# B201.net
KiCad netlist of a schematic drawn in EAGLE
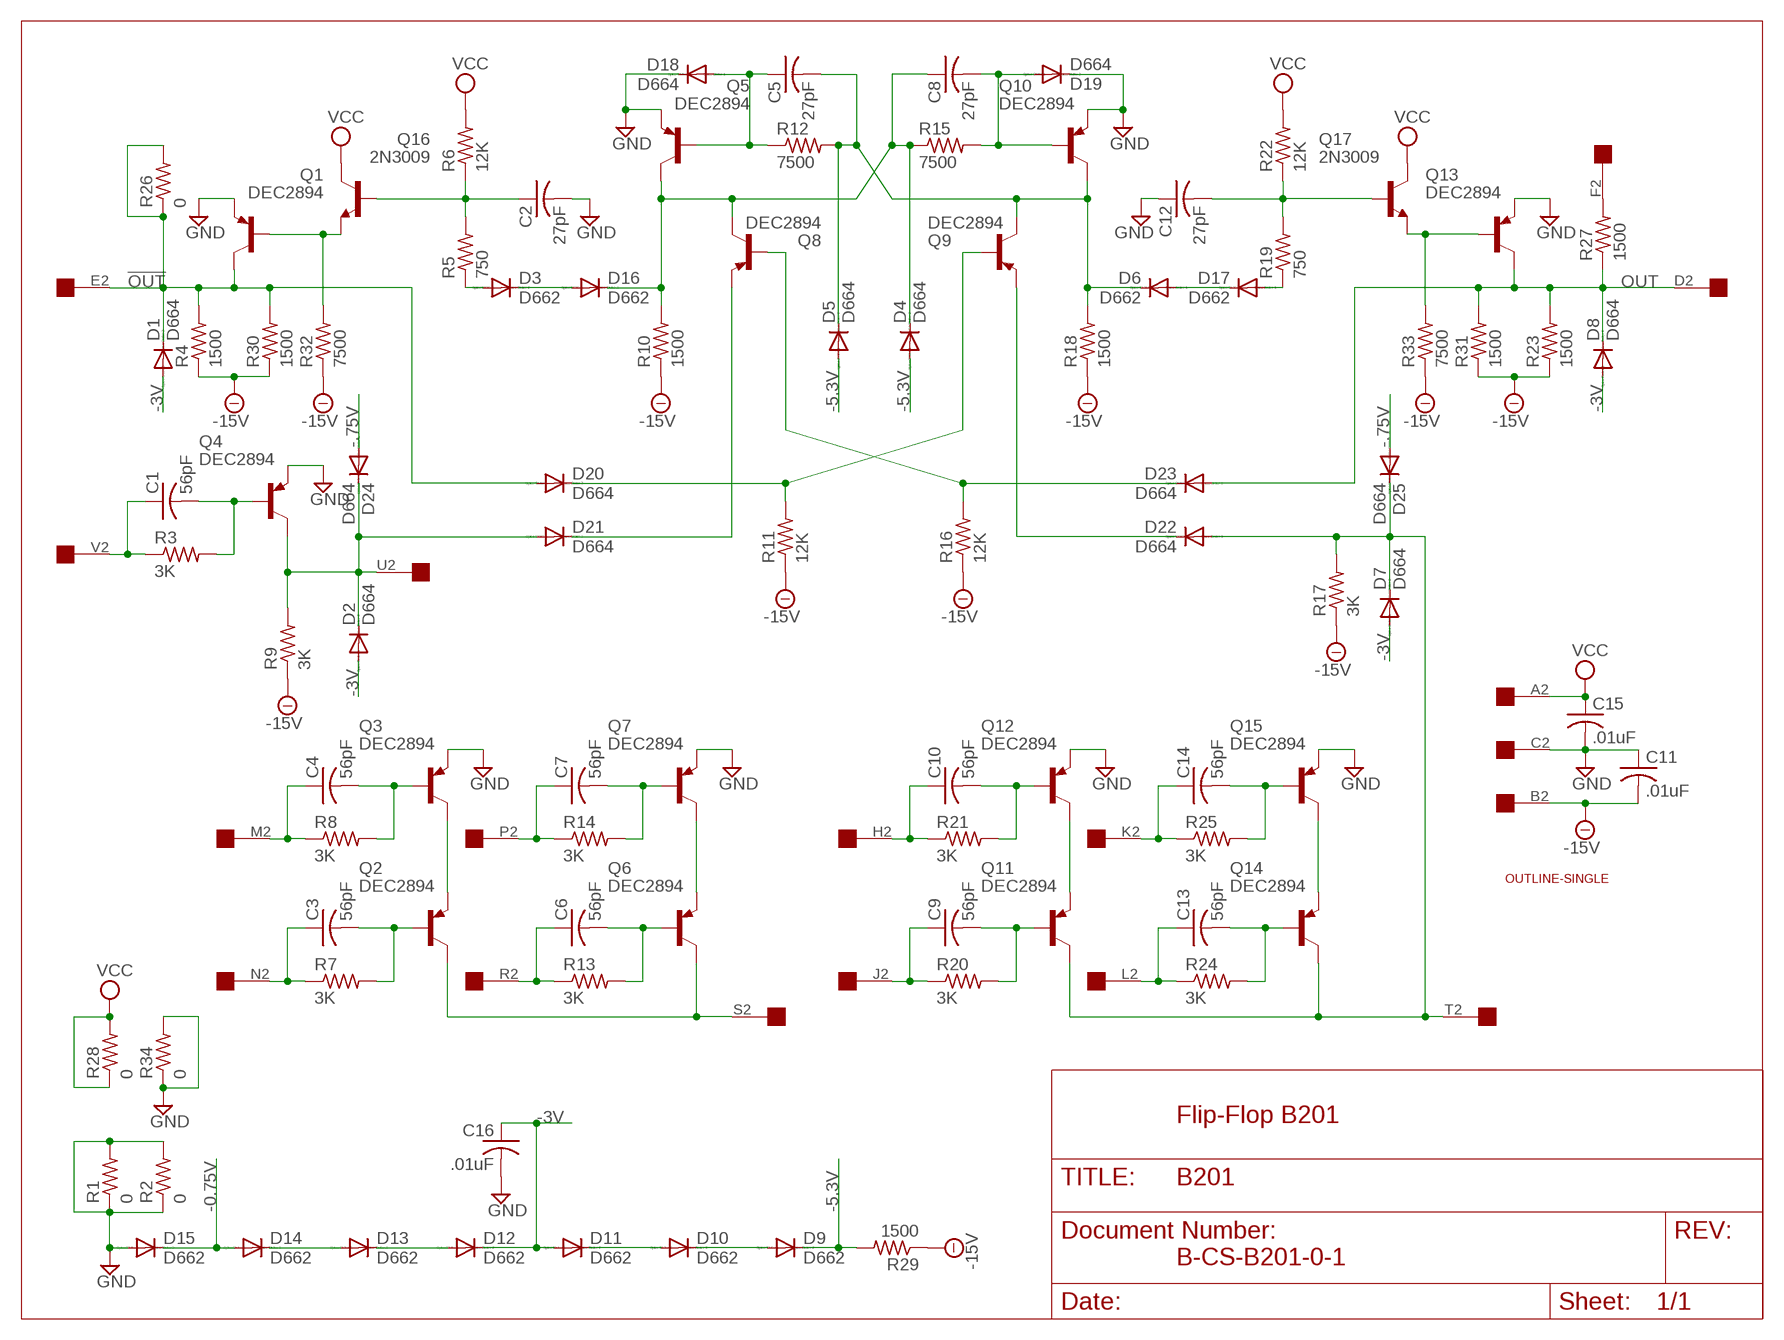
[diagram p0: schematic, sheet 1]

(export (version "E")
  (design (tool "Eeschema 10.0.6"))
  (components
    (comp (ref "C1")
      (value "56pF")
      (footprint "eagle-import:C063-025X075")
      (libsource (lib "eagle-import") (part "C-US"))
    )
    (comp (ref "C2")
      (value "27pF")
      (footprint "eagle-import:C063-025X075")
      (libsource (lib "eagle-import") (part "C-US"))
    )
    (comp (ref "C3")
      (value "56pF")
      (footprint "eagle-import:C063-025X075")
      (libsource (lib "eagle-import") (part "C-US"))
    )
    (comp (ref "C4")
      (value "56pF")
      (footprint "eagle-import:C063-025X075")
      (libsource (lib "eagle-import") (part "C-US"))
    )
    (comp (ref "C5")
      (value "27pF")
      (footprint "eagle-import:C063-025X075")
      (libsource (lib "eagle-import") (part "C-US"))
    )
    (comp (ref "C6")
      (value "56pF")
      (footprint "eagle-import:C063-025X075")
      (libsource (lib "eagle-import") (part "C-US"))
    )
    (comp (ref "C7")
      (value "56pF")
      (footprint "eagle-import:C063-025X075")
      (libsource (lib "eagle-import") (part "C-US"))
    )
    (comp (ref "C8")
      (value "27pF")
      (footprint "eagle-import:C063-025X075")
      (libsource (lib "eagle-import") (part "C-US"))
    )
    (comp (ref "C9")
      (value "56pF")
      (footprint "eagle-import:C063-025X075")
      (libsource (lib "eagle-import") (part "C-US"))
    )
    (comp (ref "C10")
      (value "56pF")
      (footprint "eagle-import:C063-025X075")
      (libsource (lib "eagle-import") (part "C-US"))
    )
    (comp (ref "C11")
      (value ".01uF")
      (footprint "eagle-import:C063-025X075")
      (libsource (lib "eagle-import") (part "C-US"))
    )
    (comp (ref "C12")
      (value "27pF")
      (footprint "eagle-import:C063-025X075")
      (libsource (lib "eagle-import") (part "C-US"))
    )
    (comp (ref "C13")
      (value "56pF")
      (footprint "eagle-import:C063-025X075")
      (libsource (lib "eagle-import") (part "C-US"))
    )
    (comp (ref "C14")
      (value "56pF")
      (footprint "eagle-import:C063-025X075")
      (libsource (lib "eagle-import") (part "C-US"))
    )
    (comp (ref "C15")
      (value ".01uF")
      (footprint "eagle-import:C063-025X075")
      (libsource (lib "eagle-import") (part "C-US"))
    )
    (comp (ref "C16")
      (value ".01uF")
      (footprint "eagle-import:C063-025X075")
      (libsource (lib "eagle-import") (part "C-US"))
    )
    (comp (ref "D1")
      (value "D664")
      (footprint "eagle-import:DO35-10")
      (libsource (lib "eagle-import") (part "DIODE-DO35-10"))
    )
    (comp (ref "D2")
      (value "D664")
      (footprint "eagle-import:DO35-10")
      (libsource (lib "eagle-import") (part "DIODE-DO35-10"))
    )
    (comp (ref "D3")
      (value "D662")
      (footprint "eagle-import:DO35-10")
      (libsource (lib "eagle-import") (part "DIODE-DO35-10"))
    )
    (comp (ref "D4")
      (value "D664")
      (footprint "eagle-import:DO35-10")
      (libsource (lib "eagle-import") (part "DIODE-DO35-10"))
    )
    (comp (ref "D5")
      (value "D664")
      (footprint "eagle-import:DO35-10")
      (libsource (lib "eagle-import") (part "DIODE-DO35-10"))
    )
    (comp (ref "D6")
      (value "D662")
      (footprint "eagle-import:DO35-10")
      (libsource (lib "eagle-import") (part "DIODE-DO35-10"))
    )
    (comp (ref "D7")
      (value "D664")
      (footprint "eagle-import:DO35-10")
      (libsource (lib "eagle-import") (part "DIODE-DO35-10"))
    )
    (comp (ref "D8")
      (value "D664")
      (footprint "eagle-import:DO35-10")
      (libsource (lib "eagle-import") (part "DIODE-DO35-10"))
    )
    (comp (ref "D9")
      (value "D662")
      (footprint "eagle-import:DO35-10")
      (libsource (lib "eagle-import") (part "DIODE-DO35-10"))
    )
    (comp (ref "D10")
      (value "D662")
      (footprint "eagle-import:DO35-10")
      (libsource (lib "eagle-import") (part "DIODE-DO35-10"))
    )
    (comp (ref "D11")
      (value "D662")
      (footprint "eagle-import:DO35-10")
      (libsource (lib "eagle-import") (part "DIODE-DO35-10"))
    )
    (comp (ref "D12")
      (value "D662")
      (footprint "eagle-import:DO35-10")
      (libsource (lib "eagle-import") (part "DIODE-DO35-10"))
    )
    (comp (ref "D13")
      (value "D662")
      (footprint "eagle-import:DO35-10")
      (libsource (lib "eagle-import") (part "DIODE-DO35-10"))
    )
    (comp (ref "D14")
      (value "D662")
      (footprint "eagle-import:DO35-10")
      (libsource (lib "eagle-import") (part "DIODE-DO35-10"))
    )
    (comp (ref "D15")
      (value "D662")
      (footprint "eagle-import:DO35-10")
      (libsource (lib "eagle-import") (part "DIODE-DO35-10"))
    )
    (comp (ref "D16")
      (value "D662")
      (footprint "eagle-import:DO35-10")
      (libsource (lib "eagle-import") (part "DIODE-DO35-10"))
    )
    (comp (ref "D17")
      (value "D662")
      (footprint "eagle-import:DO35-10")
      (libsource (lib "eagle-import") (part "DIODE-DO35-10"))
    )
    (comp (ref "D18")
      (value "D664")
      (footprint "eagle-import:DO35-10")
      (libsource (lib "eagle-import") (part "DIODE-DO35-10"))
    )
    (comp (ref "D19")
      (value "D664")
      (footprint "eagle-import:DO35-10")
      (libsource (lib "eagle-import") (part "DIODE-DO35-10"))
    )
    (comp (ref "D20")
      (value "D664")
      (footprint "eagle-import:DO35-10")
      (libsource (lib "eagle-import") (part "DIODE-DO35-10"))
    )
    (comp (ref "D21")
      (value "D664")
      (footprint "eagle-import:DO35-10")
      (libsource (lib "eagle-import") (part "DIODE-DO35-10"))
    )
    (comp (ref "D22")
      (value "D664")
      (footprint "eagle-import:DO35-10")
      (libsource (lib "eagle-import") (part "DIODE-DO35-10"))
    )
    (comp (ref "D23")
      (value "D664")
      (footprint "eagle-import:DO35-10")
      (libsource (lib "eagle-import") (part "DIODE-DO35-10"))
    )
    (comp (ref "D24")
      (value "D664")
      (footprint "eagle-import:DO35-10")
      (libsource (lib "eagle-import") (part "DIODE-DO35-10"))
    )
    (comp (ref "D25")
      (value "D664")
      (footprint "eagle-import:DO35-10")
      (libsource (lib "eagle-import") (part "DIODE-DO35-10"))
    )
    (comp (ref "Q1")
      (value "DEC2894")
      (footprint "eagle-import:TO5")
      (libsource (lib "eagle-import") (part "-PNP-TO5"))
    )
    (comp (ref "Q2")
      (value "DEC2894")
      (footprint "eagle-import:TO5")
      (libsource (lib "eagle-import") (part "-PNP-TO5"))
    )
    (comp (ref "Q3")
      (value "DEC2894")
      (footprint "eagle-import:TO5")
      (libsource (lib "eagle-import") (part "-PNP-TO5"))
    )
    (comp (ref "Q4")
      (value "DEC2894")
      (footprint "eagle-import:TO5")
      (libsource (lib "eagle-import") (part "-PNP-TO5"))
    )
    (comp (ref "Q5")
      (value "DEC2894")
      (footprint "eagle-import:TO5")
      (libsource (lib "eagle-import") (part "-PNP-TO5"))
    )
    (comp (ref "Q6")
      (value "DEC2894")
      (footprint "eagle-import:TO5")
      (libsource (lib "eagle-import") (part "-PNP-TO5"))
    )
    (comp (ref "Q7")
      (value "DEC2894")
      (footprint "eagle-import:TO5")
      (libsource (lib "eagle-import") (part "-PNP-TO5"))
    )
    (comp (ref "Q8")
      (value "DEC2894")
      (footprint "eagle-import:TO5")
      (libsource (lib "eagle-import") (part "-PNP-TO5"))
    )
    (comp (ref "Q9")
      (value "DEC2894")
      (footprint "eagle-import:TO5")
      (libsource (lib "eagle-import") (part "-PNP-TO5"))
    )
    (comp (ref "Q10")
      (value "DEC2894")
      (footprint "eagle-import:TO5")
      (libsource (lib "eagle-import") (part "-PNP-TO5"))
    )
    (comp (ref "Q11")
      (value "DEC2894")
      (footprint "eagle-import:TO5")
      (libsource (lib "eagle-import") (part "-PNP-TO5"))
    )
    (comp (ref "Q12")
      (value "DEC2894")
      (footprint "eagle-import:TO5")
      (libsource (lib "eagle-import") (part "-PNP-TO5"))
    )
    (comp (ref "Q13")
      (value "DEC2894")
      (footprint "eagle-import:TO5")
      (libsource (lib "eagle-import") (part "-PNP-TO5"))
    )
    (comp (ref "Q14")
      (value "DEC2894")
      (footprint "eagle-import:TO5")
      (libsource (lib "eagle-import") (part "-PNP-TO5"))
    )
    (comp (ref "Q15")
      (value "DEC2894")
      (footprint "eagle-import:TO5")
      (libsource (lib "eagle-import") (part "-PNP-TO5"))
    )
    (comp (ref "Q16")
      (value "2N3009")
      (footprint "eagle-import:TO5")
      (libsource (lib "eagle-import") (part "-NPN-TO5"))
    )
    (comp (ref "Q17")
      (value "2N3009")
      (footprint "eagle-import:TO5")
      (libsource (lib "eagle-import") (part "-NPN-TO5"))
    )
    (comp (ref "R1")
      (value "0")
      (footprint "eagle-import:0207_10")
      (libsource (lib "eagle-import") (part "R-US_0207/10"))
    )
    (comp (ref "R2")
      (value "0")
      (footprint "eagle-import:0207_10")
      (libsource (lib "eagle-import") (part "R-US_0207/10"))
    )
    (comp (ref "R3")
      (value "3K")
      (footprint "eagle-import:0207_10")
      (libsource (lib "eagle-import") (part "R-US_0207/10"))
    )
    (comp (ref "R4")
      (value "1500")
      (footprint "eagle-import:0207_10")
      (libsource (lib "eagle-import") (part "R-US_0207/10"))
    )
    (comp (ref "R5")
      (value "750")
      (footprint "eagle-import:0207_10")
      (libsource (lib "eagle-import") (part "R-US_0207/10"))
    )
    (comp (ref "R6")
      (value "12K")
      (footprint "eagle-import:0207_10")
      (libsource (lib "eagle-import") (part "R-US_0207/10"))
    )
    (comp (ref "R7")
      (value "3K")
      (footprint "eagle-import:0207_10")
      (libsource (lib "eagle-import") (part "R-US_0207/10"))
    )
    (comp (ref "R8")
      (value "3K")
      (footprint "eagle-import:0207_10")
      (libsource (lib "eagle-import") (part "R-US_0207/10"))
    )
    (comp (ref "R9")
      (value "3K")
      (footprint "eagle-import:0207_10")
      (libsource (lib "eagle-import") (part "R-US_0207/10"))
    )
    (comp (ref "R10")
      (value "1500")
      (footprint "eagle-import:0207_10")
      (libsource (lib "eagle-import") (part "R-US_0207/10"))
    )
    (comp (ref "R11")
      (value "12K")
      (footprint "eagle-import:0207_10")
      (libsource (lib "eagle-import") (part "R-US_0207/10"))
    )
    (comp (ref "R12")
      (value "7500")
      (footprint "eagle-import:0207_10")
      (libsource (lib "eagle-import") (part "R-US_0207/10"))
    )
    (comp (ref "R13")
      (value "3K")
      (footprint "eagle-import:0207_10")
      (libsource (lib "eagle-import") (part "R-US_0207/10"))
    )
    (comp (ref "R14")
      (value "3K")
      (footprint "eagle-import:0207_10")
      (libsource (lib "eagle-import") (part "R-US_0207/10"))
    )
    (comp (ref "R15")
      (value "7500")
      (footprint "eagle-import:0207_10")
      (libsource (lib "eagle-import") (part "R-US_0207/10"))
    )
    (comp (ref "R16")
      (value "12K")
      (footprint "eagle-import:0207_10")
      (libsource (lib "eagle-import") (part "R-US_0207/10"))
    )
    (comp (ref "R17")
      (value "3K")
      (footprint "eagle-import:0207_10")
      (libsource (lib "eagle-import") (part "R-US_0207/10"))
    )
    (comp (ref "R18")
      (value "1500")
      (footprint "eagle-import:0207_10")
      (libsource (lib "eagle-import") (part "R-US_0207/10"))
    )
    (comp (ref "R19")
      (value "750")
      (footprint "eagle-import:0207_10")
      (libsource (lib "eagle-import") (part "R-US_0207/10"))
    )
    (comp (ref "R20")
      (value "3K")
      (footprint "eagle-import:0207_10")
      (libsource (lib "eagle-import") (part "R-US_0207/10"))
    )
    (comp (ref "R21")
      (value "3K")
      (footprint "eagle-import:0207_10")
      (libsource (lib "eagle-import") (part "R-US_0207/10"))
    )
    (comp (ref "R22")
      (value "12K")
      (footprint "eagle-import:0207_10")
      (libsource (lib "eagle-import") (part "R-US_0207/10"))
    )
    (comp (ref "R23")
      (value "1500")
      (footprint "eagle-import:0207_10")
      (libsource (lib "eagle-import") (part "R-US_0207/10"))
    )
    (comp (ref "R24")
      (value "3K")
      (footprint "eagle-import:0207_10")
      (libsource (lib "eagle-import") (part "R-US_0207/10"))
    )
    (comp (ref "R25")
      (value "3K")
      (footprint "eagle-import:0207_10")
      (libsource (lib "eagle-import") (part "R-US_0207/10"))
    )
    (comp (ref "R26")
      (value "0")
      (footprint "eagle-import:0207_10")
      (libsource (lib "eagle-import") (part "R-US_0207/10"))
    )
    (comp (ref "R27")
      (value "1500")
      (footprint "eagle-import:0207_10")
      (libsource (lib "eagle-import") (part "R-US_0207/10"))
    )
    (comp (ref "R28")
      (value "0")
      (footprint "eagle-import:0207_10")
      (libsource (lib "eagle-import") (part "R-US_0207/10"))
    )
    (comp (ref "R29")
      (value "1500")
      (footprint "eagle-import:0207_10")
      (libsource (lib "eagle-import") (part "R-US_0207/10"))
    )
    (comp (ref "R30")
      (value "1500")
      (footprint "eagle-import:0207_10")
      (libsource (lib "eagle-import") (part "R-US_0207/10"))
    )
    (comp (ref "R31")
      (value "1500")
      (footprint "eagle-import:0207_10")
      (libsource (lib "eagle-import") (part "R-US_0207/10"))
    )
    (comp (ref "R32")
      (value "7500")
      (footprint "eagle-import:0207_10")
      (libsource (lib "eagle-import") (part "R-US_0207/10"))
    )
    (comp (ref "R33")
      (value "7500")
      (footprint "eagle-import:0207_10")
      (libsource (lib "eagle-import") (part "R-US_0207/10"))
    )
    (comp (ref "R34")
      (value "0")
      (footprint "eagle-import:0207_10")
      (libsource (lib "eagle-import") (part "R-US_0207/10"))
    )
    (comp (ref "U$1")
      (value "OUTLINE-SINGLE")
      (footprint "eagle-import:SINGLE")
      (libsource (lib "eagle-import") (part "OUTLINE-SINGLE"))
    )
    (comp (ref "U$2")
      (value "EDGE-1")
      (footprint "eagle-import:EDGE-CON1")
      (libsource (lib "eagle-import") (part "EDGE-1"))
    )
  )
  (nets
    (net (code "1") (name "-15V") (class "Default")
      (node (ref "C11") (pin "2") (pinfunction "2_2") (pintype "passive"))
      (node (ref "R10") (pin "1") (pinfunction "1_1") (pintype "passive"))
      (node (ref "R11") (pin "1") (pinfunction "1_1") (pintype "passive"))
      (node (ref "R16") (pin "1") (pinfunction "1_1") (pintype "passive"))
      (node (ref "R17") (pin "1") (pinfunction "1_1") (pintype "passive"))
      (node (ref "R18") (pin "1") (pinfunction "1_1") (pintype "passive"))
      (node (ref "R23") (pin "1") (pinfunction "1_1") (pintype "passive"))
      (node (ref "R29") (pin "1") (pinfunction "1_1") (pintype "passive"))
      (node (ref "R30") (pin "1") (pinfunction "1_1") (pintype "passive"))
      (node (ref "R31") (pin "1") (pinfunction "1_1") (pintype "passive"))
      (node (ref "R32") (pin "1") (pinfunction "1_1") (pintype "passive"))
      (node (ref "R33") (pin "1") (pinfunction "1_1") (pintype "passive"))
      (node (ref "R4") (pin "1") (pinfunction "1_1") (pintype "passive"))
      (node (ref "R9") (pin "1") (pinfunction "1_1") (pintype "passive"))
      (node (ref "U$2") (pin "B2") (pinfunction "1_B2") (pintype "bidirectional"))
    )
    (net (code "2") (name "/-.75V") (class "Default")
      (node (ref "D24") (pin "A") (pinfunction "A_A") (pintype "passive"))
      (node (ref "D25") (pin "A") (pinfunction "A_A") (pintype "passive"))
    )
    (net (code "3") (name "/-0.75V") (class "Default")
      (node (ref "D14") (pin "A") (pinfunction "A_A") (pintype "passive"))
      (node (ref "D15") (pin "C") (pinfunction "C_C") (pintype "passive"))
    )
    (net (code "4") (name "/-3V") (class "Default")
      (node (ref "C16") (pin "1") (pinfunction "1_1") (pintype "passive"))
      (node (ref "D1") (pin "A") (pinfunction "A_A") (pintype "passive"))
      (node (ref "D11") (pin "A") (pinfunction "A_A") (pintype "passive"))
      (node (ref "D12") (pin "C") (pinfunction "C_C") (pintype "passive"))
      (node (ref "D2") (pin "A") (pinfunction "A_A") (pintype "passive"))
      (node (ref "D7") (pin "A") (pinfunction "A_A") (pintype "passive"))
      (node (ref "D8") (pin "A") (pinfunction "A_A") (pintype "passive"))
    )
    (net (code "5") (name "/-5.3V") (class "Default")
      (node (ref "D4") (pin "A") (pinfunction "A_A") (pintype "passive"))
      (node (ref "D5") (pin "A") (pinfunction "A_A") (pintype "passive"))
      (node (ref "D9") (pin "C") (pinfunction "C_C") (pintype "passive"))
      (node (ref "R29") (pin "2") (pinfunction "2_2") (pintype "passive"))
    )
    (net (code "6") (name "/OUT") (class "Default")
      (node (ref "D23") (pin "A") (pinfunction "A_A") (pintype "passive"))
      (node (ref "D8") (pin "C") (pinfunction "C_C") (pintype "passive"))
      (node (ref "Q13") (pin "3") (pinfunction "C_3") (pintype "passive"))
      (node (ref "R23") (pin "2") (pinfunction "2_2") (pintype "passive"))
      (node (ref "R27") (pin "1") (pinfunction "1_1") (pintype "passive"))
      (node (ref "R31") (pin "2") (pinfunction "2_2") (pintype "passive"))
      (node (ref "U$2") (pin "D2") (pinfunction "1_D2") (pintype "bidirectional"))
    )
    (net (code "7") (name "/~{OUT}") (class "Default")
      (node (ref "D1") (pin "C") (pinfunction "C_C") (pintype "passive"))
      (node (ref "D20") (pin "A") (pinfunction "A_A") (pintype "passive"))
      (node (ref "Q1") (pin "3") (pinfunction "C_3") (pintype "passive"))
      (node (ref "R26") (pin "1") (pinfunction "1_1") (pintype "passive"))
      (node (ref "R26") (pin "2") (pinfunction "2_2") (pintype "passive"))
      (node (ref "R30") (pin "2") (pinfunction "2_2") (pintype "passive"))
      (node (ref "R4") (pin "2") (pinfunction "2_2") (pintype "passive"))
      (node (ref "U$2") (pin "E2") (pinfunction "1_E2") (pintype "bidirectional"))
    )
    (net (code "8") (name "GND") (class "Default")
      (node (ref "C11") (pin "1") (pinfunction "1_1") (pintype "passive"))
      (node (ref "C12") (pin "1") (pinfunction "1_1") (pintype "passive"))
      (node (ref "C15") (pin "2") (pinfunction "2_2") (pintype "passive"))
      (node (ref "C16") (pin "2") (pinfunction "2_2") (pintype "passive"))
      (node (ref "C2") (pin "2") (pinfunction "2_2") (pintype "passive"))
      (node (ref "D15") (pin "A") (pinfunction "A_A") (pintype "passive"))
      (node (ref "D18") (pin "C") (pinfunction "C_C") (pintype "passive"))
      (node (ref "D19") (pin "C") (pinfunction "C_C") (pintype "passive"))
      (node (ref "Q1") (pin "1") (pinfunction "E_1") (pintype "passive"))
      (node (ref "Q10") (pin "1") (pinfunction "E_1") (pintype "passive"))
      (node (ref "Q12") (pin "1") (pinfunction "E_1") (pintype "passive"))
      (node (ref "Q13") (pin "1") (pinfunction "E_1") (pintype "passive"))
      (node (ref "Q15") (pin "1") (pinfunction "E_1") (pintype "passive"))
      (node (ref "Q3") (pin "1") (pinfunction "E_1") (pintype "passive"))
      (node (ref "Q4") (pin "1") (pinfunction "E_1") (pintype "passive"))
      (node (ref "Q5") (pin "1") (pinfunction "E_1") (pintype "passive"))
      (node (ref "Q7") (pin "1") (pinfunction "E_1") (pintype "passive"))
      (node (ref "R1") (pin "1") (pinfunction "1_1") (pintype "passive"))
      (node (ref "R1") (pin "2") (pinfunction "2_2") (pintype "passive"))
      (node (ref "R2") (pin "1") (pinfunction "1_1") (pintype "passive"))
      (node (ref "R2") (pin "2") (pinfunction "2_2") (pintype "passive"))
      (node (ref "R34") (pin "1") (pinfunction "1_1") (pintype "passive"))
      (node (ref "R34") (pin "2") (pinfunction "2_2") (pintype "passive"))
      (node (ref "U$2") (pin "C2") (pinfunction "1_C2") (pintype "bidirectional"))
    )
    (net (code "9") (name "Net-(D3-PadA)") (class "Default")
      (node (ref "D3") (pin "A") (pinfunction "A_A") (pintype "passive"))
      (node (ref "R5") (pin "1") (pinfunction "1_1") (pintype "passive"))
    )
    (net (code "10") (name "Net-(D10-PadA)") (class "Default")
      (node (ref "D10") (pin "A") (pinfunction "A_A") (pintype "passive"))
      (node (ref "D11") (pin "C") (pinfunction "C_C") (pintype "passive"))
    )
    (net (code "11") (name "Net-(D10-PadC)") (class "Default")
      (node (ref "D10") (pin "C") (pinfunction "C_C") (pintype "passive"))
      (node (ref "D9") (pin "A") (pinfunction "A_A") (pintype "passive"))
    )
    (net (code "12") (name "Net-(D12-PadA)") (class "Default")
      (node (ref "D12") (pin "A") (pinfunction "A_A") (pintype "passive"))
      (node (ref "D13") (pin "C") (pinfunction "C_C") (pintype "passive"))
    )
    (net (code "13") (name "Net-(D13-PadA)") (class "Default")
      (node (ref "D13") (pin "A") (pinfunction "A_A") (pintype "passive"))
      (node (ref "D14") (pin "C") (pinfunction "C_C") (pintype "passive"))
    )
    (net (code "14") (name "Net-(D16-PadA)") (class "Default")
      (node (ref "D16") (pin "A") (pinfunction "A_A") (pintype "passive"))
      (node (ref "D3") (pin "C") (pinfunction "C_C") (pintype "passive"))
    )
    (net (code "15") (name "Net-(D17-PadA)") (class "Default")
      (node (ref "D17") (pin "A") (pinfunction "A_A") (pintype "passive"))
      (node (ref "R19") (pin "1") (pinfunction "1_1") (pintype "passive"))
    )
    (net (code "16") (name "Net-(D17-PadC)") (class "Default")
      (node (ref "D17") (pin "C") (pinfunction "C_C") (pintype "passive"))
      (node (ref "D6") (pin "A") (pinfunction "A_A") (pintype "passive"))
    )
    (net (code "17") (name "Net-(Q1-B)") (class "Default")
      (node (ref "Q1") (pin "2") (pinfunction "B_2") (pintype "passive"))
      (node (ref "Q16") (pin "1") (pinfunction "E_1") (pintype "passive"))
      (node (ref "R32") (pin "2") (pinfunction "2_2") (pintype "passive"))
    )
    (net (code "18") (name "Net-(Q2-B)") (class "Default")
      (node (ref "C3") (pin "2") (pinfunction "2_2") (pintype "passive"))
      (node (ref "Q2") (pin "2") (pinfunction "B_2") (pintype "passive"))
      (node (ref "R7") (pin "2") (pinfunction "2_2") (pintype "passive"))
    )
    (net (code "19") (name "Net-(Q2-C)") (class "Default")
      (node (ref "Q2") (pin "3") (pinfunction "C_3") (pintype "passive"))
      (node (ref "Q6") (pin "3") (pinfunction "C_3") (pintype "passive"))
      (node (ref "U$2") (pin "S2") (pinfunction "1_S2") (pintype "bidirectional"))
    )
    (net (code "20") (name "Net-(Q2-E)") (class "Default")
      (node (ref "Q2") (pin "1") (pinfunction "E_1") (pintype "passive"))
      (node (ref "Q3") (pin "3") (pinfunction "C_3") (pintype "passive"))
    )
    (net (code "21") (name "Net-(Q3-B)") (class "Default")
      (node (ref "C4") (pin "2") (pinfunction "2_2") (pintype "passive"))
      (node (ref "Q3") (pin "2") (pinfunction "B_2") (pintype "passive"))
      (node (ref "R8") (pin "2") (pinfunction "2_2") (pintype "passive"))
    )
    (net (code "22") (name "Net-(Q4-B)") (class "Default")
      (node (ref "C1") (pin "2") (pinfunction "2_2") (pintype "passive"))
      (node (ref "Q4") (pin "2") (pinfunction "B_2") (pintype "passive"))
      (node (ref "R3") (pin "2") (pinfunction "2_2") (pintype "passive"))
    )
    (net (code "23") (name "Net-(Q4-C)") (class "Default")
      (node (ref "D2") (pin "C") (pinfunction "C_C") (pintype "passive"))
      (node (ref "D21") (pin "A") (pinfunction "A_A") (pintype "passive"))
      (node (ref "D24") (pin "C") (pinfunction "C_C") (pintype "passive"))
      (node (ref "Q4") (pin "3") (pinfunction "C_3") (pintype "passive"))
      (node (ref "R9") (pin "2") (pinfunction "2_2") (pintype "passive"))
      (node (ref "U$2") (pin "U2") (pinfunction "1_U2") (pintype "bidirectional"))
    )
    (net (code "24") (name "Net-(Q5-B)") (class "Default")
      (node (ref "C5") (pin "1") (pinfunction "1_1") (pintype "passive"))
      (node (ref "D18") (pin "A") (pinfunction "A_A") (pintype "passive"))
      (node (ref "Q5") (pin "2") (pinfunction "B_2") (pintype "passive"))
      (node (ref "R12") (pin "1") (pinfunction "1_1") (pintype "passive"))
    )
    (net (code "25") (name "Net-(Q5-C)") (class "Default")
      (node (ref "C8") (pin "1") (pinfunction "1_1") (pintype "passive"))
      (node (ref "D16") (pin "C") (pinfunction "C_C") (pintype "passive"))
      (node (ref "D4") (pin "C") (pinfunction "C_C") (pintype "passive"))
      (node (ref "Q5") (pin "3") (pinfunction "C_3") (pintype "passive"))
      (node (ref "Q8") (pin "3") (pinfunction "C_3") (pintype "passive"))
      (node (ref "R10") (pin "2") (pinfunction "2_2") (pintype "passive"))
      (node (ref "R15") (pin "1") (pinfunction "1_1") (pintype "passive"))
    )
    (net (code "26") (name "Net-(Q6-B)") (class "Default")
      (node (ref "C6") (pin "2") (pinfunction "2_2") (pintype "passive"))
      (node (ref "Q6") (pin "2") (pinfunction "B_2") (pintype "passive"))
      (node (ref "R13") (pin "2") (pinfunction "2_2") (pintype "passive"))
    )
    (net (code "27") (name "Net-(Q6-E)") (class "Default")
      (node (ref "Q6") (pin "1") (pinfunction "E_1") (pintype "passive"))
      (node (ref "Q7") (pin "3") (pinfunction "C_3") (pintype "passive"))
    )
    (net (code "28") (name "Net-(Q7-B)") (class "Default")
      (node (ref "C7") (pin "2") (pinfunction "2_2") (pintype "passive"))
      (node (ref "Q7") (pin "2") (pinfunction "B_2") (pintype "passive"))
      (node (ref "R14") (pin "2") (pinfunction "2_2") (pintype "passive"))
    )
    (net (code "29") (name "Net-(Q8-B)") (class "Default")
      (node (ref "D23") (pin "C") (pinfunction "C_C") (pintype "passive"))
      (node (ref "Q8") (pin "2") (pinfunction "B_2") (pintype "passive"))
      (node (ref "R16") (pin "2") (pinfunction "2_2") (pintype "passive"))
    )
    (net (code "30") (name "Net-(Q8-E)") (class "Default")
      (node (ref "D21") (pin "C") (pinfunction "C_C") (pintype "passive"))
      (node (ref "Q8") (pin "1") (pinfunction "E_1") (pintype "passive"))
    )
    (net (code "31") (name "Net-(Q9-B)") (class "Default")
      (node (ref "D20") (pin "C") (pinfunction "C_C") (pintype "passive"))
      (node (ref "Q9") (pin "2") (pinfunction "B_2") (pintype "passive"))
      (node (ref "R11") (pin "2") (pinfunction "2_2") (pintype "passive"))
    )
    (net (code "32") (name "Net-(Q9-E)") (class "Default")
      (node (ref "D22") (pin "C") (pinfunction "C_C") (pintype "passive"))
      (node (ref "Q9") (pin "1") (pinfunction "E_1") (pintype "passive"))
    )
    (net (code "33") (name "Net-(Q10-B)") (class "Default")
      (node (ref "C8") (pin "2") (pinfunction "2_2") (pintype "passive"))
      (node (ref "D19") (pin "A") (pinfunction "A_A") (pintype "passive"))
      (node (ref "Q10") (pin "2") (pinfunction "B_2") (pintype "passive"))
      (node (ref "R15") (pin "2") (pinfunction "2_2") (pintype "passive"))
    )
    (net (code "34") (name "Net-(Q10-C)") (class "Default")
      (node (ref "C5") (pin "2") (pinfunction "2_2") (pintype "passive"))
      (node (ref "D5") (pin "C") (pinfunction "C_C") (pintype "passive"))
      (node (ref "D6") (pin "C") (pinfunction "C_C") (pintype "passive"))
      (node (ref "Q10") (pin "3") (pinfunction "C_3") (pintype "passive"))
      (node (ref "Q9") (pin "3") (pinfunction "C_3") (pintype "passive"))
      (node (ref "R12") (pin "2") (pinfunction "2_2") (pintype "passive"))
      (node (ref "R18") (pin "2") (pinfunction "2_2") (pintype "passive"))
    )
    (net (code "35") (name "Net-(Q11-B)") (class "Default")
      (node (ref "C9") (pin "2") (pinfunction "2_2") (pintype "passive"))
      (node (ref "Q11") (pin "2") (pinfunction "B_2") (pintype "passive"))
      (node (ref "R20") (pin "2") (pinfunction "2_2") (pintype "passive"))
    )
    (net (code "36") (name "Net-(Q11-C)") (class "Default")
      (node (ref "D22") (pin "A") (pinfunction "A_A") (pintype "passive"))
      (node (ref "D25") (pin "C") (pinfunction "C_C") (pintype "passive"))
      (node (ref "D7") (pin "C") (pinfunction "C_C") (pintype "passive"))
      (node (ref "Q11") (pin "3") (pinfunction "C_3") (pintype "passive"))
      (node (ref "Q14") (pin "3") (pinfunction "C_3") (pintype "passive"))
      (node (ref "R17") (pin "2") (pinfunction "2_2") (pintype "passive"))
      (node (ref "U$2") (pin "T2") (pinfunction "1_T2") (pintype "bidirectional"))
    )
    (net (code "37") (name "Net-(Q11-E)") (class "Default")
      (node (ref "Q11") (pin "1") (pinfunction "E_1") (pintype "passive"))
      (node (ref "Q12") (pin "3") (pinfunction "C_3") (pintype "passive"))
    )
    (net (code "38") (name "Net-(Q12-B)") (class "Default")
      (node (ref "C10") (pin "2") (pinfunction "2_2") (pintype "passive"))
      (node (ref "Q12") (pin "2") (pinfunction "B_2") (pintype "passive"))
      (node (ref "R21") (pin "2") (pinfunction "2_2") (pintype "passive"))
    )
    (net (code "39") (name "Net-(Q13-B)") (class "Default")
      (node (ref "Q13") (pin "2") (pinfunction "B_2") (pintype "passive"))
      (node (ref "Q17") (pin "1") (pinfunction "E_1") (pintype "passive"))
      (node (ref "R33") (pin "2") (pinfunction "2_2") (pintype "passive"))
    )
    (net (code "40") (name "Net-(Q14-B)") (class "Default")
      (node (ref "C13") (pin "2") (pinfunction "2_2") (pintype "passive"))
      (node (ref "Q14") (pin "2") (pinfunction "B_2") (pintype "passive"))
      (node (ref "R24") (pin "2") (pinfunction "2_2") (pintype "passive"))
    )
    (net (code "41") (name "Net-(Q14-E)") (class "Default")
      (node (ref "Q14") (pin "1") (pinfunction "E_1") (pintype "passive"))
      (node (ref "Q15") (pin "3") (pinfunction "C_3") (pintype "passive"))
    )
    (net (code "42") (name "Net-(Q15-B)") (class "Default")
      (node (ref "C14") (pin "2") (pinfunction "2_2") (pintype "passive"))
      (node (ref "Q15") (pin "2") (pinfunction "B_2") (pintype "passive"))
      (node (ref "R25") (pin "2") (pinfunction "2_2") (pintype "passive"))
    )
    (net (code "43") (name "Net-(Q16-B)") (class "Default")
      (node (ref "C2") (pin "1") (pinfunction "1_1") (pintype "passive"))
      (node (ref "Q16") (pin "2") (pinfunction "B_2") (pintype "passive"))
      (node (ref "R5") (pin "2") (pinfunction "2_2") (pintype "passive"))
      (node (ref "R6") (pin "1") (pinfunction "1_1") (pintype "passive"))
    )
    (net (code "44") (name "Net-(Q17-B)") (class "Default")
      (node (ref "C12") (pin "2") (pinfunction "2_2") (pintype "passive"))
      (node (ref "Q17") (pin "2") (pinfunction "B_2") (pintype "passive"))
      (node (ref "R19") (pin "2") (pinfunction "2_2") (pintype "passive"))
      (node (ref "R22") (pin "1") (pinfunction "1_1") (pintype "passive"))
    )
    (net (code "45") (name "Net-(U$2F-1)") (class "Default")
      (node (ref "R27") (pin "2") (pinfunction "2_2") (pintype "passive"))
      (node (ref "U$2") (pin "F2") (pinfunction "1_F2") (pintype "bidirectional"))
    )
    (net (code "46") (name "Net-(U$2G-1)") (class "Default")
      (node (ref "C10") (pin "1") (pinfunction "1_1") (pintype "passive"))
      (node (ref "R21") (pin "1") (pinfunction "1_1") (pintype "passive"))
      (node (ref "U$2") (pin "H2") (pinfunction "1_H2") (pintype "bidirectional"))
    )
    (net (code "47") (name "Net-(U$2H-1)") (class "Default")
      (node (ref "C9") (pin "1") (pinfunction "1_1") (pintype "passive"))
      (node (ref "R20") (pin "1") (pinfunction "1_1") (pintype "passive"))
      (node (ref "U$2") (pin "J2") (pinfunction "1_J2") (pintype "bidirectional"))
    )
    (net (code "48") (name "Net-(U$2I-1)") (class "Default")
      (node (ref "C14") (pin "1") (pinfunction "1_1") (pintype "passive"))
      (node (ref "R25") (pin "1") (pinfunction "1_1") (pintype "passive"))
      (node (ref "U$2") (pin "K2") (pinfunction "1_K2") (pintype "bidirectional"))
    )
    (net (code "49") (name "Net-(U$2J-1)") (class "Default")
      (node (ref "C13") (pin "1") (pinfunction "1_1") (pintype "passive"))
      (node (ref "R24") (pin "1") (pinfunction "1_1") (pintype "passive"))
      (node (ref "U$2") (pin "L2") (pinfunction "1_L2") (pintype "bidirectional"))
    )
    (net (code "50") (name "Net-(U$2K-1)") (class "Default")
      (node (ref "C4") (pin "1") (pinfunction "1_1") (pintype "passive"))
      (node (ref "R8") (pin "1") (pinfunction "1_1") (pintype "passive"))
      (node (ref "U$2") (pin "M2") (pinfunction "1_M2") (pintype "bidirectional"))
    )
    (net (code "51") (name "Net-(U$2L-1)") (class "Default")
      (node (ref "C3") (pin "1") (pinfunction "1_1") (pintype "passive"))
      (node (ref "R7") (pin "1") (pinfunction "1_1") (pintype "passive"))
      (node (ref "U$2") (pin "N2") (pinfunction "1_N2") (pintype "bidirectional"))
    )
    (net (code "52") (name "Net-(U$2M-1)") (class "Default")
      (node (ref "C7") (pin "1") (pinfunction "1_1") (pintype "passive"))
      (node (ref "R14") (pin "1") (pinfunction "1_1") (pintype "passive"))
      (node (ref "U$2") (pin "P2") (pinfunction "1_P2") (pintype "bidirectional"))
    )
    (net (code "53") (name "Net-(U$2N-1)") (class "Default")
      (node (ref "C6") (pin "1") (pinfunction "1_1") (pintype "passive"))
      (node (ref "R13") (pin "1") (pinfunction "1_1") (pintype "passive"))
      (node (ref "U$2") (pin "R2") (pinfunction "1_R2") (pintype "bidirectional"))
    )
    (net (code "54") (name "Net-(U$2R-1)") (class "Default")
      (node (ref "C1") (pin "1") (pinfunction "1_1") (pintype "passive"))
      (node (ref "R3") (pin "1") (pinfunction "1_1") (pintype "passive"))
      (node (ref "U$2") (pin "V2") (pinfunction "1_V2") (pintype "bidirectional"))
    )
    (net (code "55") (name "VCC") (class "Default")
      (node (ref "C15") (pin "1") (pinfunction "1_1") (pintype "passive"))
      (node (ref "Q16") (pin "3") (pinfunction "C_3") (pintype "passive"))
      (node (ref "Q17") (pin "3") (pinfunction "C_3") (pintype "passive"))
      (node (ref "R22") (pin "2") (pinfunction "2_2") (pintype "passive"))
      (node (ref "R28") (pin "1") (pinfunction "1_1") (pintype "passive"))
      (node (ref "R28") (pin "2") (pinfunction "2_2") (pintype "passive"))
      (node (ref "R6") (pin "2") (pinfunction "2_2") (pintype "passive"))
      (node (ref "U$2") (pin "A2") (pinfunction "1_A2") (pintype "bidirectional"))
    )
  )
)
